# ECG_12ch.net
KiCad netlist of a schematic drawn in Altium Designer
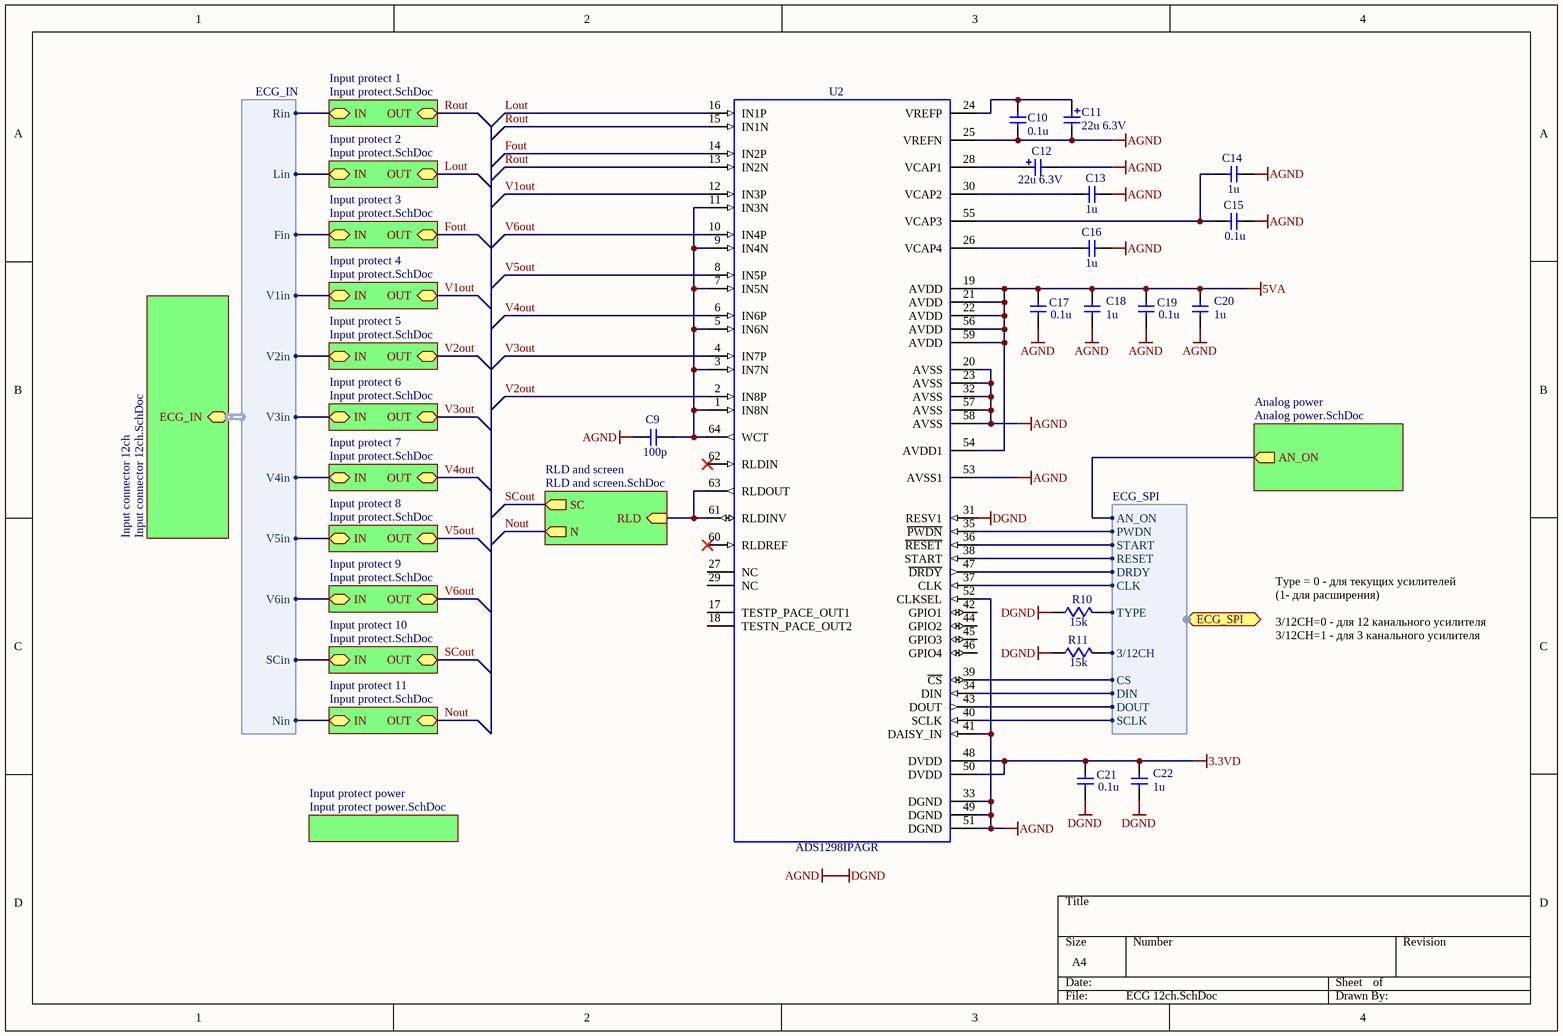
[diagram p0: ECG 12ch.SchDoc]

(export (version "E")
  (design (tool "Eeschema 10.0.6"))
  (components
    (comp (ref "C9") (value "100p") (footprint "SMD/C/0603") (libsource (lib "My_lib") (part "Capacitor")))
    (comp (ref "C10") (value "0.1u") (footprint "SMD/C/0603") (libsource (lib "My_lib") (part "Capacitor")))
    (comp (ref "C11")
      (value "22u 6.3V")
      (footprint "SMD/C/TAJ-A")
      (libsource (lib "My_lib") (part "Capacitor Pol"))
    )
    (comp (ref "C12")
      (value "22u 6.3V")
      (footprint "SMD/C/TAJ-A")
      (libsource (lib "My_lib") (part "Capacitor Pol"))
    )
    (comp (ref "C13") (value "1u") (footprint "SMD/C/0603") (libsource (lib "My_lib") (part "Capacitor")))
    (comp (ref "C14") (value "1u") (footprint "SMD/C/0603") (libsource (lib "My_lib") (part "Capacitor")))
    (comp (ref "C15") (value "0.1u") (footprint "SMD/C/0603") (libsource (lib "My_lib") (part "Capacitor")))
    (comp (ref "C16") (value "1u") (footprint "SMD/C/0603") (libsource (lib "My_lib") (part "Capacitor")))
    (comp (ref "C17") (value "0.1u") (footprint "SMD/C/0603") (libsource (lib "My_lib") (part "Capacitor")))
    (comp (ref "C18") (value "1u") (footprint "SMD/C/0603") (libsource (lib "My_lib") (part "Capacitor")))
    (comp (ref "C19") (value "0.1u") (footprint "SMD/C/0603") (libsource (lib "My_lib") (part "Capacitor")))
    (comp (ref "C20") (value "1u") (footprint "SMD/C/0603") (libsource (lib "My_lib") (part "Capacitor")))
    (comp (ref "C21") (value "0.1u") (footprint "SMD/C/0603") (libsource (lib "My_lib") (part "Capacitor")))
    (comp (ref "C22") (value "1u") (footprint "SMD/C/0603") (libsource (lib "My_lib") (part "Capacitor")))
    (comp (ref "R10") (value "15k") (footprint "SMD/R/0603") (libsource (lib "My_lib") (part "Resistor")))
    (comp (ref "R11") (value "15k") (footprint "SMD/R/0603") (libsource (lib "My_lib") (part "Resistor")))
    (comp (ref "U2")
      (value "ADS1298IPAGR")
      (footprint "SMD/QFP64/0.5MMP/10x10MM/12X12MMWP")
      (description "Interleaving Continuous Conduction Mode PFC Controller")
      (libsource (lib "My_lib") (part "ADS1298IPAGR"))
    )
  )
  (nets
    (net (code "3") (name "/3{slash}12CH") (class "Default")
      (node (ref "R11") (pin "2") (pinfunction "2_2") (pintype "passive"))
    )
    (net (code "5") (name "/CLK") (class "Default")
      (node (ref "U2") (pin "37") (pinfunction "CLK_37") (pintype "input"))
    )
    (net (code "6") (name "/CS") (class "Default")
      (node (ref "U2") (pin "39") (pinfunction "~{CS}_39") (pintype "bidirectional"))
    )
    (net (code "7") (name "/DIN") (class "Default")
      (node (ref "U2") (pin "34") (pinfunction "DIN_34") (pintype "input"))
    )
    (net (code "8") (name "/DOUT") (class "Default")
      (node (ref "U2") (pin "43") (pinfunction "DOUT_43") (pintype "output"))
    )
    (net (code "9") (name "/DRDY") (class "Default")
      (node (ref "U2") (pin "47") (pinfunction "~{DRDY}_47") (pintype "output"))
    )
    (net (code "11") (name "/Fout") (class "Default")
      (node (ref "U2") (pin "14") (pinfunction "IN2P_14") (pintype "input"))
    )
    (net (code "13") (name "/Lout") (class "Default")
      (node (ref "U2") (pin "16") (pinfunction "IN1P_16") (pintype "input"))
    )
    (net (code "16") (name "/PWDN") (class "Default")
      (node (ref "U2") (pin "35") (pinfunction "~{PWDN}_35") (pintype "input"))
    )
    (net (code "17") (name "/RESET") (class "Default")
      (node (ref "U2") (pin "38") (pinfunction "START_38") (pintype "input"))
    )
    (net (code "18") (name "/RLD") (class "Default")
      (node (ref "U2") (pin "61") (pinfunction "RLDINV_61") (pintype "bidirectional"))
      (node (ref "U2") (pin "63") (pinfunction "RLDOUT_63") (pintype "output"))
    )
    (net (code "20") (name "/Rout") (class "Default")
      (node (ref "U2") (pin "13") (pinfunction "IN2N_13") (pintype "input"))
      (node (ref "U2") (pin "15") (pinfunction "IN1N_15") (pintype "input"))
    )
    (net (code "21") (name "/SCLK") (class "Default")
      (node (ref "U2") (pin "40") (pinfunction "SCLK_40") (pintype "input"))
    )
    (net (code "24") (name "/START") (class "Default")
      (node (ref "U2") (pin "36") (pinfunction "~{RESET}_36") (pintype "input"))
    )
    (net (code "25") (name "/TYPE") (class "Default")
      (node (ref "R10") (pin "2") (pinfunction "2_2") (pintype "passive"))
    )
    (net (code "27") (name "/V1out") (class "Default")
      (node (ref "U2") (pin "12") (pinfunction "IN3P_12") (pintype "input"))
    )
    (net (code "29") (name "/V2out") (class "Default")
      (node (ref "U2") (pin "2") (pinfunction "IN8P_2") (pintype "input"))
    )
    (net (code "31") (name "/V3out") (class "Default")
      (node (ref "U2") (pin "4") (pinfunction "IN7P_4") (pintype "input"))
    )
    (net (code "33") (name "/V4out") (class "Default")
      (node (ref "U2") (pin "6") (pinfunction "IN6P_6") (pintype "input"))
    )
    (net (code "35") (name "/V5out") (class "Default")
      (node (ref "U2") (pin "8") (pinfunction "IN5P_8") (pintype "input"))
    )
    (net (code "37") (name "/V6out") (class "Default")
      (node (ref "U2") (pin "10") (pinfunction "IN4P_10") (pintype "input"))
    )
    (net (code "40") (name "3.3VD") (class "Default")
      (node (ref "C21") (pin "2") (pinfunction "2_2") (pintype "passive"))
      (node (ref "C22") (pin "2") (pinfunction "2_2") (pintype "passive"))
      (node (ref "U2") (pin "48") (pinfunction "DVDD_48") (pintype "power_in"))
      (node (ref "U2") (pin "50") (pinfunction "DVDD_50") (pintype "power_in"))
    )
    (net (code "41") (name "5VA") (class "Default")
      (node (ref "C17") (pin "2") (pinfunction "2_2") (pintype "passive"))
      (node (ref "C18") (pin "2") (pinfunction "2_2") (pintype "passive"))
      (node (ref "C19") (pin "2") (pinfunction "2_2") (pintype "passive"))
      (node (ref "C20") (pin "2") (pinfunction "2_2") (pintype "passive"))
      (node (ref "U2") (pin "19") (pinfunction "AVDD_19") (pintype "passive"))
      (node (ref "U2") (pin "21") (pinfunction "AVDD_21") (pintype "passive"))
      (node (ref "U2") (pin "22") (pinfunction "AVDD_22") (pintype "passive"))
      (node (ref "U2") (pin "54") (pinfunction "AVDD1_54") (pintype "passive"))
      (node (ref "U2") (pin "56") (pinfunction "AVDD_56") (pintype "passive"))
      (node (ref "U2") (pin "59") (pinfunction "AVDD_59") (pintype "passive"))
    )
    (net (code "42") (name "AGND") (class "Default")
      (node (ref "C10") (pin "1") (pinfunction "1_1") (pintype "passive"))
      (node (ref "C11") (pin "M") (pinfunction "M_M") (pintype "passive"))
      (node (ref "C12") (pin "M") (pinfunction "M_M") (pintype "passive"))
      (node (ref "C13") (pin "1") (pinfunction "1_1") (pintype "passive"))
      (node (ref "C14") (pin "1") (pinfunction "1_1") (pintype "passive"))
      (node (ref "C15") (pin "1") (pinfunction "1_1") (pintype "passive"))
      (node (ref "C16") (pin "1") (pinfunction "1_1") (pintype "passive"))
      (node (ref "C17") (pin "1") (pinfunction "1_1") (pintype "passive"))
      (node (ref "C18") (pin "1") (pinfunction "1_1") (pintype "passive"))
      (node (ref "C19") (pin "1") (pinfunction "1_1") (pintype "passive"))
      (node (ref "C20") (pin "1") (pinfunction "1_1") (pintype "passive"))
      (node (ref "C21") (pin "1") (pinfunction "1_1") (pintype "passive"))
      (node (ref "C22") (pin "1") (pinfunction "1_1") (pintype "passive"))
      (node (ref "C9") (pin "2") (pinfunction "2_2") (pintype "passive"))
      (node (ref "R10") (pin "1") (pinfunction "1_1") (pintype "passive"))
      (node (ref "R11") (pin "1") (pinfunction "1_1") (pintype "passive"))
      (node (ref "U2") (pin "20") (pinfunction "AVSS_20") (pintype "passive"))
      (node (ref "U2") (pin "23") (pinfunction "AVSS_23") (pintype "passive"))
      (node (ref "U2") (pin "25") (pinfunction "VREFN_25") (pintype "power_in"))
      (node (ref "U2") (pin "31") (pinfunction "RESV1_31") (pintype "input"))
      (node (ref "U2") (pin "32") (pinfunction "AVSS_32") (pintype "passive"))
      (node (ref "U2") (pin "33") (pinfunction "DGND_33") (pintype "power_in"))
      (node (ref "U2") (pin "41") (pinfunction "DAISY_IN_41") (pintype "input"))
      (node (ref "U2") (pin "49") (pinfunction "DGND_49") (pintype "power_in"))
      (node (ref "U2") (pin "51") (pinfunction "DGND_51") (pintype "power_in"))
      (node (ref "U2") (pin "52") (pinfunction "CLKSEL_52") (pintype "input"))
      (node (ref "U2") (pin "53") (pinfunction "AVSS1_53") (pintype "passive"))
      (node (ref "U2") (pin "57") (pinfunction "AVSS_57") (pintype "passive"))
      (node (ref "U2") (pin "58") (pinfunction "AVSS_58") (pintype "passive"))
    )
    (net (code "43") (name "Net-(U2-IN3N)") (class "Default")
      (node (ref "C9") (pin "1") (pinfunction "1_1") (pintype "passive"))
      (node (ref "U2") (pin "1") (pinfunction "IN8N_1") (pintype "input"))
      (node (ref "U2") (pin "11") (pinfunction "IN3N_11") (pintype "input"))
      (node (ref "U2") (pin "3") (pinfunction "IN7N_3") (pintype "input"))
      (node (ref "U2") (pin "5") (pinfunction "IN6N_5") (pintype "input"))
      (node (ref "U2") (pin "64") (pinfunction "WCT_64") (pintype "output"))
      (node (ref "U2") (pin "7") (pinfunction "IN5N_7") (pintype "input"))
      (node (ref "U2") (pin "9") (pinfunction "IN4N_9") (pintype "input"))
    )
    (net (code "44") (name "Net-(U2-VCAP1)") (class "Default")
      (node (ref "C12") (pin "P") (pinfunction "P_P") (pintype "passive"))
      (node (ref "U2") (pin "28") (pinfunction "VCAP1_28") (pintype "passive"))
    )
    (net (code "45") (name "Net-(U2-VCAP2)") (class "Default")
      (node (ref "C13") (pin "2") (pinfunction "2_2") (pintype "passive"))
      (node (ref "U2") (pin "30") (pinfunction "VCAP2_30") (pintype "passive"))
    )
    (net (code "46") (name "Net-(U2-VCAP3)") (class "Default")
      (node (ref "C14") (pin "2") (pinfunction "2_2") (pintype "passive"))
      (node (ref "C15") (pin "2") (pinfunction "2_2") (pintype "passive"))
      (node (ref "U2") (pin "55") (pinfunction "VCAP3_55") (pintype "passive"))
    )
    (net (code "47") (name "Net-(U2-VCAP4)") (class "Default")
      (node (ref "C16") (pin "2") (pinfunction "2_2") (pintype "passive"))
      (node (ref "U2") (pin "26") (pinfunction "VCAP4_26") (pintype "passive"))
    )
    (net (code "48") (name "Net-(U2-VREFP)") (class "Default")
      (node (ref "C10") (pin "2") (pinfunction "2_2") (pintype "passive"))
      (node (ref "C11") (pin "P") (pinfunction "P_P") (pintype "passive"))
      (node (ref "U2") (pin "24") (pinfunction "VREFP_24") (pintype "power_in"))
    )
    (net (code "49") (name "unconnected-(U2-GPIO1-Pad42)") (class "Default")
      (node (ref "U2") (pin "42") (pinfunction "GPIO1_42") (pintype "bidirectional"))
    )
    (net (code "50") (name "unconnected-(U2-GPIO2-Pad44)") (class "Default")
      (node (ref "U2") (pin "44") (pinfunction "GPIO2_44") (pintype "bidirectional"))
    )
    (net (code "51") (name "unconnected-(U2-GPIO3-Pad45)") (class "Default")
      (node (ref "U2") (pin "45") (pinfunction "GPIO3_45") (pintype "bidirectional"))
    )
    (net (code "52") (name "unconnected-(U2-GPIO4-Pad46)") (class "Default")
      (node (ref "U2") (pin "46") (pinfunction "GPIO4_46") (pintype "bidirectional"))
    )
    (net (code "53") (name "unconnected-(U2-NC-Pad27)") (class "Default")
      (node (ref "U2") (pin "27") (pinfunction "NC_27") (pintype "passive"))
    )
    (net (code "54") (name "unconnected-(U2-NC-Pad29)") (class "Default")
      (node (ref "U2") (pin "29") (pinfunction "NC_29") (pintype "passive"))
    )
    (net (code "55") (name "unconnected-(U2-RLDIN-Pad62)") (class "Default")
      (node (ref "U2") (pin "62") (pinfunction "RLDIN_62") (pintype "input+no_connect"))
    )
    (net (code "56") (name "unconnected-(U2-RLDREF-Pad60)") (class "Default")
      (node (ref "U2") (pin "60") (pinfunction "RLDREF_60") (pintype "input+no_connect"))
    )
    (net (code "57") (name "unconnected-(U2-TESTN_PACE_OUT2-Pad18)") (class "Default")
      (node (ref "U2") (pin "18") (pinfunction "TESTN_PACE_OUT2_18") (pintype "passive"))
    )
    (net (code "58") (name "unconnected-(U2-TESTP_PACE_OUT1-Pad17)") (class "Default")
      (node (ref "U2") (pin "17") (pinfunction "TESTP_PACE_OUT1_17") (pintype "passive"))
    )
  )
)
